# schema.net
KiCad netlist of a schematic drawn in EAGLE
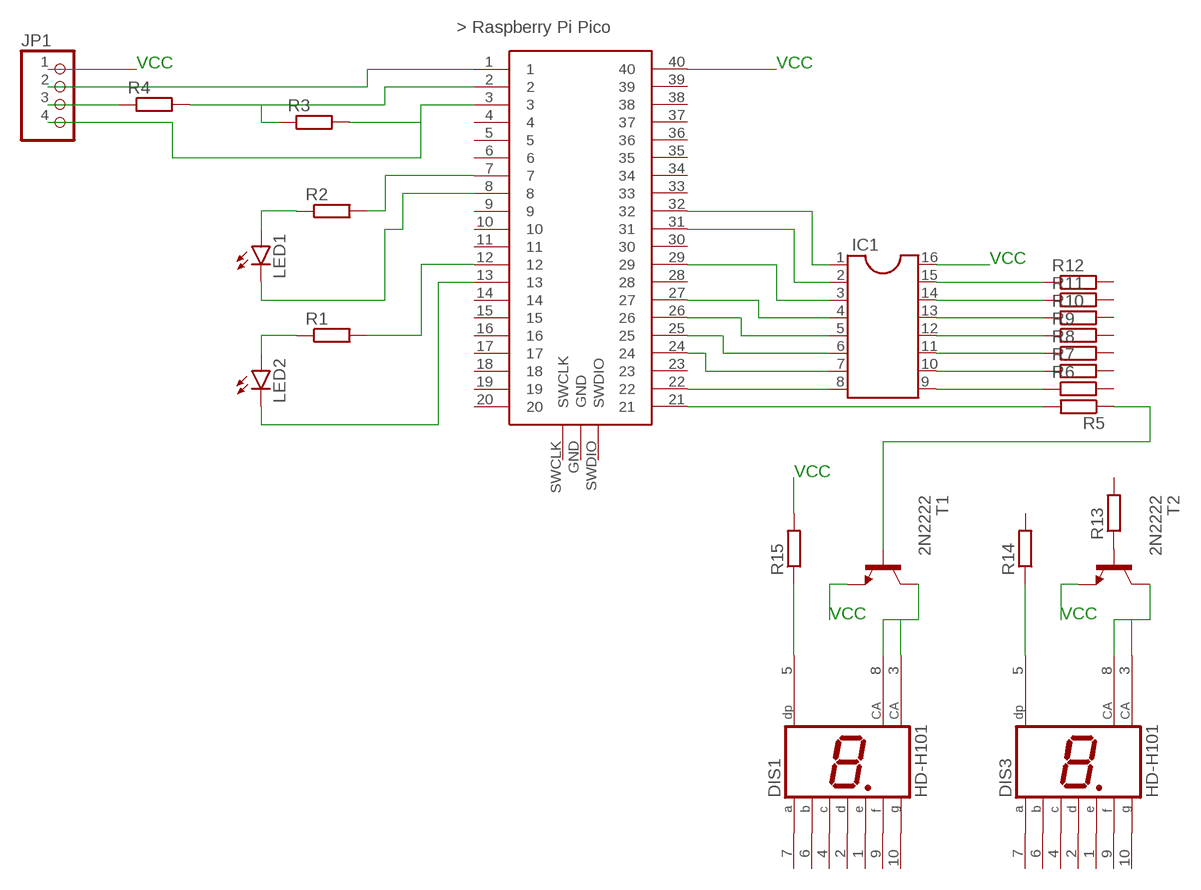
[diagram p0: schematic, sheet 1]

(export (version "E")
  (design (tool "Eeschema 10.0.6"))
  (components
    (comp (ref "DIS1")
      (value "HD-H101")
      (footprint "eagle-import:HDSP-M")
      (libsource (lib "eagle-import") (part "HD-H101"))
    )
    (comp (ref "DIS3")
      (value "HD-H101")
      (footprint "eagle-import:HDSP-M")
      (libsource (lib "eagle-import") (part "HD-H101"))
    )
    (comp (ref "IC1")
      (value "DIL16")
      (footprint "eagle-import:DIL16")
      (libsource (lib "eagle-import") (part "DIL16"))
    )
    (comp (ref "JP1")
      (value "PINHD-1X4")
      (footprint "eagle-import:1X04")
      (libsource (lib "eagle-import") (part "PINHD-1X4"))
    )
    (comp (ref "LED1")
      (value "LED5MM")
      (footprint "eagle-import:LED5MM")
      (libsource (lib "eagle-import") (part "LED5MM"))
    )
    (comp (ref "LED2")
      (value "LED5MM")
      (footprint "eagle-import:LED5MM")
      (libsource (lib "eagle-import") (part "LED5MM"))
    )
    (comp (ref "R1")
      (value "R-EU_0204/7")
      (footprint "eagle-import:0204_7")
      (libsource (lib "eagle-import") (part "R-EU_0204/7"))
    )
    (comp (ref "R2")
      (value "R-EU_0204/7")
      (footprint "eagle-import:0204_7")
      (libsource (lib "eagle-import") (part "R-EU_0204/7"))
    )
    (comp (ref "R3")
      (value "R-EU_0204/7")
      (footprint "eagle-import:0204_7")
      (libsource (lib "eagle-import") (part "R-EU_0204/7"))
    )
    (comp (ref "R4")
      (value "R-EU_0204/7")
      (footprint "eagle-import:0204_7")
      (libsource (lib "eagle-import") (part "R-EU_0204/7"))
    )
    (comp (ref "R5")
      (value "R-EU_0204/7")
      (footprint "eagle-import:0204_7")
      (libsource (lib "eagle-import") (part "R-EU_0204/7"))
    )
    (comp (ref "R6")
      (value "R-EU_0204/7")
      (footprint "eagle-import:0204_7")
      (libsource (lib "eagle-import") (part "R-EU_0204/7"))
    )
    (comp (ref "R7")
      (value "R-EU_0204/7")
      (footprint "eagle-import:0204_7")
      (libsource (lib "eagle-import") (part "R-EU_0204/7"))
    )
    (comp (ref "R8")
      (value "R-EU_0204/7")
      (footprint "eagle-import:0204_7")
      (libsource (lib "eagle-import") (part "R-EU_0204/7"))
    )
    (comp (ref "R9")
      (value "R-EU_0204/7")
      (footprint "eagle-import:0204_7")
      (libsource (lib "eagle-import") (part "R-EU_0204/7"))
    )
    (comp (ref "R10")
      (value "R-EU_0204/7")
      (footprint "eagle-import:0204_7")
      (libsource (lib "eagle-import") (part "R-EU_0204/7"))
    )
    (comp (ref "R11")
      (value "R-EU_0204/7")
      (footprint "eagle-import:0204_7")
      (libsource (lib "eagle-import") (part "R-EU_0204/7"))
    )
    (comp (ref "R12")
      (value "R-EU_0204/7")
      (footprint "eagle-import:0204_7")
      (libsource (lib "eagle-import") (part "R-EU_0204/7"))
    )
    (comp (ref "R13")
      (value "R-EU_0204/7")
      (footprint "eagle-import:0204_7")
      (libsource (lib "eagle-import") (part "R-EU_0204/7"))
    )
    (comp (ref "R14")
      (value "R-EU_0204/7")
      (footprint "eagle-import:0204_7")
      (libsource (lib "eagle-import") (part "R-EU_0204/7"))
    )
    (comp (ref "R15")
      (value "R-EU_0204/7")
      (footprint "eagle-import:0204_7")
      (libsource (lib "eagle-import") (part "R-EU_0204/7"))
    )
    (comp (ref "T1")
      (value "2N2222")
      (footprint "eagle-import:TO18")
      (libsource (lib "eagle-import") (part "2N2222"))
    )
    (comp (ref "T2")
      (value "2N2222")
      (footprint "eagle-import:TO18")
      (libsource (lib "eagle-import") (part "2N2222"))
    )
    (comp (ref "U$1")
      (value "RASPBERRY-PI-PICO_TH")
      (footprint "eagle-import:FT_RASPBERRY-PI-PICO_TH")
      (libsource (lib "eagle-import") (part "RASPBERRY-PI-PICO_TH"))
    )
  )
  (nets
    (net (code "1") (name "Net-(DIS1-DP)") (class "Default")
      (node (ref "DIS1") (pin "5") (pinfunction "DP_5") (pintype "passive"))
      (node (ref "R15") (pin "1") (pinfunction "1_1") (pintype "passive"))
    )
    (net (code "2") (name "Net-(DIS3-DP)") (class "Default")
      (node (ref "DIS3") (pin "5") (pinfunction "DP_5") (pintype "passive"))
      (node (ref "R14") (pin "1") (pinfunction "1_1") (pintype "passive"))
    )
    (net (code "3") (name "Net-(IC1-Pad1)") (class "Default")
      (node (ref "IC1") (pin "1") (pinfunction "1_1") (pintype "passive"))
      (node (ref "U$1") (pin "32") (pinfunction "32_32") (pintype "bidirectional"))
    )
    (net (code "4") (name "Net-(IC1-Pad2)") (class "Default")
      (node (ref "IC1") (pin "2") (pinfunction "2_2") (pintype "passive"))
      (node (ref "U$1") (pin "31") (pinfunction "31_31") (pintype "bidirectional"))
    )
    (net (code "5") (name "Net-(IC1-Pad3)") (class "Default")
      (node (ref "IC1") (pin "3") (pinfunction "3_3") (pintype "passive"))
      (node (ref "U$1") (pin "29") (pinfunction "29_29") (pintype "bidirectional"))
    )
    (net (code "6") (name "Net-(IC1-Pad4)") (class "Default")
      (node (ref "IC1") (pin "4") (pinfunction "4_4") (pintype "passive"))
      (node (ref "U$1") (pin "27") (pinfunction "27_27") (pintype "bidirectional"))
    )
    (net (code "7") (name "Net-(IC1-Pad5)") (class "Default")
      (node (ref "IC1") (pin "5") (pinfunction "5_5") (pintype "passive"))
      (node (ref "U$1") (pin "26") (pinfunction "26_26") (pintype "bidirectional"))
    )
    (net (code "8") (name "Net-(IC1-Pad6)") (class "Default")
      (node (ref "IC1") (pin "6") (pinfunction "6_6") (pintype "passive"))
      (node (ref "U$1") (pin "25") (pinfunction "25_25") (pintype "bidirectional"))
    )
    (net (code "9") (name "Net-(IC1-Pad7)") (class "Default")
      (node (ref "IC1") (pin "7") (pinfunction "7_7") (pintype "passive"))
      (node (ref "U$1") (pin "24") (pinfunction "24_24") (pintype "bidirectional"))
    )
    (net (code "10") (name "Net-(IC1-Pad8)") (class "Default")
      (node (ref "IC1") (pin "8") (pinfunction "8_8") (pintype "passive"))
      (node (ref "U$1") (pin "22") (pinfunction "22_22") (pintype "bidirectional"))
    )
    (net (code "11") (name "Net-(IC1-Pad9)") (class "Default")
      (node (ref "IC1") (pin "9") (pinfunction "9_9") (pintype "passive"))
      (node (ref "R6") (pin "1") (pinfunction "1_1") (pintype "passive"))
    )
    (net (code "12") (name "Net-(IC1-Pad10)") (class "Default")
      (node (ref "IC1") (pin "10") (pinfunction "10_10") (pintype "passive"))
      (node (ref "R7") (pin "1") (pinfunction "1_1") (pintype "passive"))
    )
    (net (code "13") (name "Net-(IC1-Pad11)") (class "Default")
      (node (ref "IC1") (pin "11") (pinfunction "11_11") (pintype "passive"))
      (node (ref "R8") (pin "1") (pinfunction "1_1") (pintype "passive"))
    )
    (net (code "14") (name "Net-(IC1-Pad12)") (class "Default")
      (node (ref "IC1") (pin "12") (pinfunction "12_12") (pintype "passive"))
      (node (ref "R9") (pin "1") (pinfunction "1_1") (pintype "passive"))
    )
    (net (code "15") (name "Net-(IC1-Pad13)") (class "Default")
      (node (ref "IC1") (pin "13") (pinfunction "13_13") (pintype "passive"))
      (node (ref "R10") (pin "1") (pinfunction "1_1") (pintype "passive"))
    )
    (net (code "16") (name "Net-(IC1-Pad14)") (class "Default")
      (node (ref "IC1") (pin "14") (pinfunction "14_14") (pintype "passive"))
      (node (ref "R11") (pin "1") (pinfunction "1_1") (pintype "passive"))
    )
    (net (code "17") (name "Net-(IC1-Pad15)") (class "Default")
      (node (ref "IC1") (pin "15") (pinfunction "15_15") (pintype "passive"))
      (node (ref "R12") (pin "1") (pinfunction "1_1") (pintype "passive"))
    )
    (net (code "18") (name "Net-(JP1-Pad2)") (class "Default")
      (node (ref "JP1") (pin "2") (pinfunction "2_2") (pintype "passive"))
      (node (ref "U$1") (pin "1") (pinfunction "1_1") (pintype "bidirectional"))
    )
    (net (code "19") (name "Net-(JP1-Pad3)") (class "Default")
      (node (ref "JP1") (pin "3") (pinfunction "3_3") (pintype "passive"))
      (node (ref "R4") (pin "1") (pinfunction "1_1") (pintype "passive"))
    )
    (net (code "20") (name "Net-(JP1-Pad4)") (class "Default")
      (node (ref "JP1") (pin "4") (pinfunction "4_4") (pintype "passive"))
      (node (ref "R3") (pin "2") (pinfunction "2_2") (pintype "passive"))
      (node (ref "U$1") (pin "3") (pinfunction "3_3") (pintype "bidirectional"))
    )
    (net (code "21") (name "Net-(LED1-C)") (class "Default")
      (node (ref "LED1") (pin "K") (pinfunction "C_K") (pintype "passive"))
      (node (ref "U$1") (pin "8") (pinfunction "8_8") (pintype "bidirectional"))
    )
    (net (code "22") (name "Net-(LED1-PadA)") (class "Default")
      (node (ref "LED1") (pin "A") (pinfunction "A_A") (pintype "passive"))
      (node (ref "R2") (pin "1") (pinfunction "1_1") (pintype "passive"))
    )
    (net (code "23") (name "Net-(LED2-C)") (class "Default")
      (node (ref "LED2") (pin "K") (pinfunction "C_K") (pintype "passive"))
      (node (ref "U$1") (pin "13") (pinfunction "13_13") (pintype "bidirectional"))
    )
    (net (code "24") (name "Net-(LED2-PadA)") (class "Default")
      (node (ref "LED2") (pin "A") (pinfunction "A_A") (pintype "passive"))
      (node (ref "R1") (pin "1") (pinfunction "1_1") (pintype "passive"))
    )
    (net (code "25") (name "Net-(R1-Pad2)") (class "Default")
      (node (ref "R1") (pin "2") (pinfunction "2_2") (pintype "passive"))
      (node (ref "U$1") (pin "12") (pinfunction "12_12") (pintype "bidirectional"))
    )
    (net (code "26") (name "Net-(R2-Pad2)") (class "Default")
      (node (ref "R2") (pin "2") (pinfunction "2_2") (pintype "passive"))
      (node (ref "U$1") (pin "7") (pinfunction "7_7") (pintype "bidirectional"))
    )
    (net (code "27") (name "Net-(R3-Pad1)") (class "Default")
      (node (ref "R3") (pin "1") (pinfunction "1_1") (pintype "passive"))
      (node (ref "R4") (pin "2") (pinfunction "2_2") (pintype "passive"))
      (node (ref "U$1") (pin "2") (pinfunction "2_2") (pintype "bidirectional"))
    )
    (net (code "28") (name "Net-(R5-Pad2)") (class "Default")
      (node (ref "R5") (pin "2") (pinfunction "2_2") (pintype "passive"))
      (node (ref "U$1") (pin "21") (pinfunction "21_21") (pintype "bidirectional"))
    )
    (net (code "29") (name "Net-(T1-B)") (class "Default")
      (node (ref "R5") (pin "1") (pinfunction "1_1") (pintype "passive"))
      (node (ref "T1") (pin "2") (pinfunction "B_2") (pintype "passive"))
    )
    (net (code "30") (name "Net-(T1-C)") (class "Default")
      (node (ref "DIS1") (pin "3") (pinfunction "CA_3") (pintype "passive"))
      (node (ref "DIS1") (pin "8") (pinfunction "CA_8") (pintype "passive"))
      (node (ref "T1") (pin "3") (pinfunction "C_3") (pintype "passive"))
    )
    (net (code "31") (name "Net-(T2-B)") (class "Default")
      (node (ref "R13") (pin "1") (pinfunction "1_1") (pintype "passive"))
      (node (ref "T2") (pin "2") (pinfunction "B_2") (pintype "passive"))
    )
    (net (code "32") (name "Net-(T2-C)") (class "Default")
      (node (ref "DIS3") (pin "3") (pinfunction "CA_3") (pintype "passive"))
      (node (ref "DIS3") (pin "8") (pinfunction "CA_8") (pintype "passive"))
      (node (ref "T2") (pin "3") (pinfunction "C_3") (pintype "passive"))
    )
    (net (code "33") (name "unconnected-(DIS1-A-Pad7)") (class "Default")
      (node (ref "DIS1") (pin "7") (pinfunction "A_7") (pintype "passive"))
    )
    (net (code "34") (name "unconnected-(DIS1-B-Pad6)") (class "Default")
      (node (ref "DIS1") (pin "6") (pinfunction "B_6") (pintype "passive"))
    )
    (net (code "35") (name "unconnected-(DIS1-C-Pad4)") (class "Default")
      (node (ref "DIS1") (pin "4") (pinfunction "C_4") (pintype "passive"))
    )
    (net (code "36") (name "unconnected-(DIS1-D-Pad2)") (class "Default")
      (node (ref "DIS1") (pin "2") (pinfunction "D_2") (pintype "passive"))
    )
    (net (code "37") (name "unconnected-(DIS1-E-Pad1)") (class "Default")
      (node (ref "DIS1") (pin "1") (pinfunction "E_1") (pintype "passive"))
    )
    (net (code "38") (name "unconnected-(DIS1-F-Pad9)") (class "Default")
      (node (ref "DIS1") (pin "9") (pinfunction "F_9") (pintype "passive"))
    )
    (net (code "39") (name "unconnected-(DIS1-G-Pad10)") (class "Default")
      (node (ref "DIS1") (pin "10") (pinfunction "G_10") (pintype "passive"))
    )
    (net (code "40") (name "unconnected-(DIS3-A-Pad7)") (class "Default")
      (node (ref "DIS3") (pin "7") (pinfunction "A_7") (pintype "passive"))
    )
    (net (code "41") (name "unconnected-(DIS3-B-Pad6)") (class "Default")
      (node (ref "DIS3") (pin "6") (pinfunction "B_6") (pintype "passive"))
    )
    (net (code "42") (name "unconnected-(DIS3-C-Pad4)") (class "Default")
      (node (ref "DIS3") (pin "4") (pinfunction "C_4") (pintype "passive"))
    )
    (net (code "43") (name "unconnected-(DIS3-D-Pad2)") (class "Default")
      (node (ref "DIS3") (pin "2") (pinfunction "D_2") (pintype "passive"))
    )
    (net (code "44") (name "unconnected-(DIS3-E-Pad1)") (class "Default")
      (node (ref "DIS3") (pin "1") (pinfunction "E_1") (pintype "passive"))
    )
    (net (code "45") (name "unconnected-(DIS3-F-Pad9)") (class "Default")
      (node (ref "DIS3") (pin "9") (pinfunction "F_9") (pintype "passive"))
    )
    (net (code "46") (name "unconnected-(DIS3-G-Pad10)") (class "Default")
      (node (ref "DIS3") (pin "10") (pinfunction "G_10") (pintype "passive"))
    )
    (net (code "47") (name "unconnected-(IC1-Pad16)") (class "Default")
      (node (ref "IC1") (pin "16") (pinfunction "16_16") (pintype "passive"))
    )
    (net (code "48") (name "unconnected-(JP1-Pad1)") (class "Default")
      (node (ref "JP1") (pin "1") (pinfunction "1_1") (pintype "passive"))
    )
    (net (code "49") (name "unconnected-(R6-Pad2)") (class "Default")
      (node (ref "R6") (pin "2") (pinfunction "2_2") (pintype "passive"))
    )
    (net (code "50") (name "unconnected-(R7-Pad2)") (class "Default")
      (node (ref "R7") (pin "2") (pinfunction "2_2") (pintype "passive"))
    )
    (net (code "51") (name "unconnected-(R8-Pad2)") (class "Default")
      (node (ref "R8") (pin "2") (pinfunction "2_2") (pintype "passive"))
    )
    (net (code "52") (name "unconnected-(R9-Pad2)") (class "Default")
      (node (ref "R9") (pin "2") (pinfunction "2_2") (pintype "passive"))
    )
    (net (code "53") (name "unconnected-(R10-Pad2)") (class "Default")
      (node (ref "R10") (pin "2") (pinfunction "2_2") (pintype "passive"))
    )
    (net (code "54") (name "unconnected-(R11-Pad2)") (class "Default")
      (node (ref "R11") (pin "2") (pinfunction "2_2") (pintype "passive"))
    )
    (net (code "55") (name "unconnected-(R12-Pad2)") (class "Default")
      (node (ref "R12") (pin "2") (pinfunction "2_2") (pintype "passive"))
    )
    (net (code "56") (name "unconnected-(R13-Pad2)") (class "Default")
      (node (ref "R13") (pin "2") (pinfunction "2_2") (pintype "passive"))
    )
    (net (code "57") (name "unconnected-(R14-Pad2)") (class "Default")
      (node (ref "R14") (pin "2") (pinfunction "2_2") (pintype "passive"))
    )
    (net (code "58") (name "unconnected-(R15-Pad2)") (class "Default")
      (node (ref "R15") (pin "2") (pinfunction "2_2") (pintype "passive"))
    )
    (net (code "59") (name "unconnected-(T1-E-Pad1)") (class "Default")
      (node (ref "T1") (pin "1") (pinfunction "E_1") (pintype "passive"))
    )
    (net (code "60") (name "unconnected-(T2-E-Pad1)") (class "Default")
      (node (ref "T2") (pin "1") (pinfunction "E_1") (pintype "passive"))
    )
    (net (code "61") (name "unconnected-(U$1-Pad4)") (class "Default")
      (node (ref "U$1") (pin "4") (pinfunction "4_4") (pintype "bidirectional"))
    )
    (net (code "62") (name "unconnected-(U$1-Pad5)") (class "Default")
      (node (ref "U$1") (pin "5") (pinfunction "5_5") (pintype "bidirectional"))
    )
    (net (code "63") (name "unconnected-(U$1-Pad6)") (class "Default")
      (node (ref "U$1") (pin "6") (pinfunction "6_6") (pintype "bidirectional"))
    )
    (net (code "64") (name "unconnected-(U$1-Pad9)") (class "Default")
      (node (ref "U$1") (pin "9") (pinfunction "9_9") (pintype "bidirectional"))
    )
    (net (code "65") (name "unconnected-(U$1-Pad10)") (class "Default")
      (node (ref "U$1") (pin "10") (pinfunction "10_10") (pintype "bidirectional"))
    )
    (net (code "66") (name "unconnected-(U$1-Pad11)") (class "Default")
      (node (ref "U$1") (pin "11") (pinfunction "11_11") (pintype "bidirectional"))
    )
    (net (code "67") (name "unconnected-(U$1-Pad14)") (class "Default")
      (node (ref "U$1") (pin "14") (pinfunction "14_14") (pintype "bidirectional"))
    )
    (net (code "68") (name "unconnected-(U$1-Pad15)") (class "Default")
      (node (ref "U$1") (pin "15") (pinfunction "15_15") (pintype "bidirectional"))
    )
    (net (code "69") (name "unconnected-(U$1-Pad16)") (class "Default")
      (node (ref "U$1") (pin "16") (pinfunction "16_16") (pintype "bidirectional"))
    )
    (net (code "70") (name "unconnected-(U$1-Pad17)") (class "Default")
      (node (ref "U$1") (pin "17") (pinfunction "17_17") (pintype "bidirectional"))
    )
    (net (code "71") (name "unconnected-(U$1-Pad18)") (class "Default")
      (node (ref "U$1") (pin "18") (pinfunction "18_18") (pintype "bidirectional"))
    )
    (net (code "72") (name "unconnected-(U$1-Pad19)") (class "Default")
      (node (ref "U$1") (pin "19") (pinfunction "19_19") (pintype "bidirectional"))
    )
    (net (code "73") (name "unconnected-(U$1-Pad20)") (class "Default")
      (node (ref "U$1") (pin "20") (pinfunction "20_20") (pintype "bidirectional"))
    )
    (net (code "74") (name "unconnected-(U$1-Pad23)") (class "Default")
      (node (ref "U$1") (pin "23") (pinfunction "23_23") (pintype "bidirectional"))
    )
    (net (code "75") (name "unconnected-(U$1-Pad28)") (class "Default")
      (node (ref "U$1") (pin "28") (pinfunction "28_28") (pintype "bidirectional"))
    )
    (net (code "76") (name "unconnected-(U$1-Pad30)") (class "Default")
      (node (ref "U$1") (pin "30") (pinfunction "30_30") (pintype "bidirectional"))
    )
    (net (code "77") (name "unconnected-(U$1-Pad33)") (class "Default")
      (node (ref "U$1") (pin "33") (pinfunction "33_33") (pintype "bidirectional"))
    )
    (net (code "78") (name "unconnected-(U$1-Pad34)") (class "Default")
      (node (ref "U$1") (pin "34") (pinfunction "34_34") (pintype "bidirectional"))
    )
    (net (code "79") (name "unconnected-(U$1-Pad35)") (class "Default")
      (node (ref "U$1") (pin "35") (pinfunction "35_35") (pintype "bidirectional"))
    )
    (net (code "80") (name "unconnected-(U$1-Pad36)") (class "Default")
      (node (ref "U$1") (pin "36") (pinfunction "36_36") (pintype "bidirectional"))
    )
    (net (code "81") (name "unconnected-(U$1-Pad37)") (class "Default")
      (node (ref "U$1") (pin "37") (pinfunction "37_37") (pintype "bidirectional"))
    )
    (net (code "82") (name "unconnected-(U$1-Pad38)") (class "Default")
      (node (ref "U$1") (pin "38") (pinfunction "38_38") (pintype "bidirectional"))
    )
    (net (code "83") (name "unconnected-(U$1-Pad39)") (class "Default")
      (node (ref "U$1") (pin "39") (pinfunction "39_39") (pintype "bidirectional"))
    )
    (net (code "84") (name "unconnected-(U$1-Pad40)") (class "Default")
      (node (ref "U$1") (pin "40") (pinfunction "40_40") (pintype "bidirectional"))
    )
    (net (code "85") (name "unconnected-(U$1-PadGND)") (class "Default")
      (node (ref "U$1") (pin "GND") (pinfunction "GND_GND") (pintype "bidirectional"))
    )
    (net (code "86") (name "unconnected-(U$1-PadSWCLK)") (class "Default")
      (node (ref "U$1") (pin "SWCLK") (pinfunction "SWCLK_SWCLK") (pintype "bidirectional"))
    )
    (net (code "87") (name "unconnected-(U$1-PadSWDIO)") (class "Default")
      (node (ref "U$1") (pin "SWDIO") (pinfunction "SWDIO_SWDIO") (pintype "bidirectional"))
    )
  )
)
